# pHCircuit.net
KiCad netlist of a schematic drawn in Altium Designer
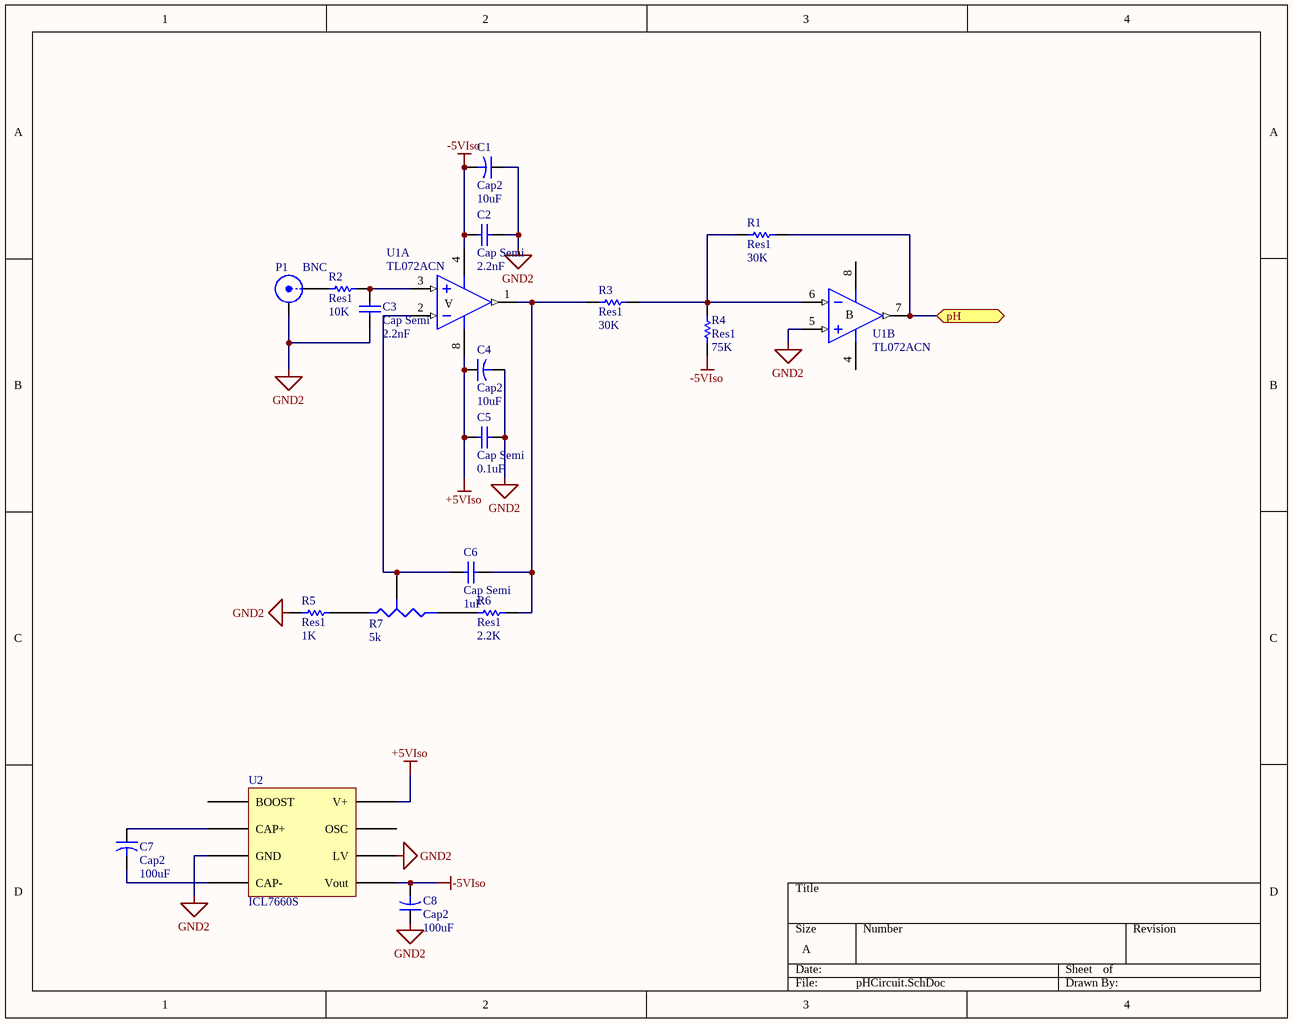
[diagram p0: pHCircuit.SchDoc]

(export (version "E")
  (design (tool "Eeschema 10.0.6"))
  (components
    (comp (ref "C1")
      (value "Cap2")
      (footprint "CAPC3216L")
      (description "Capacitor")
      (fields (field (name "ALTIUM_VALUE") "10uF") (field (name "PUBLISHER") "Altium Limited"))
      (libsource (lib "Miscellaneous Devices") (part "Cap2"))
    )
    (comp (ref "C2")
      (value "Cap Semi")
      (footprint "RESC2012L")
      (description "Capacitor (Semiconductor SIM Model)")
      (fields (field (name "ALTIUM_VALUE") "2.2nF") (field (name "PUBLISHER") "Altium Limited"))
      (libsource (lib "Miscellaneous Devices") (part "Cap Semi"))
    )
    (comp (ref "C3")
      (value "Cap Semi")
      (footprint "RESC2012L")
      (description "Capacitor (Semiconductor SIM Model)")
      (fields (field (name "ALTIUM_VALUE") "2.2nF") (field (name "PUBLISHER") "Altium Limited"))
      (libsource (lib "Miscellaneous Devices") (part "Cap Semi"))
    )
    (comp (ref "C4")
      (value "Cap2")
      (footprint "CAPC3216L")
      (description "Capacitor")
      (fields (field (name "ALTIUM_VALUE") "10uF") (field (name "PUBLISHER") "Altium Limited"))
      (libsource (lib "Miscellaneous Devices") (part "Cap2"))
    )
    (comp (ref "C5")
      (value "Cap Semi")
      (footprint "RESC2012L")
      (description "Capacitor (Semiconductor SIM Model)")
      (fields (field (name "ALTIUM_VALUE") "0.1uF") (field (name "PUBLISHER") "Altium Limited"))
      (libsource (lib "Miscellaneous Devices") (part "Cap Semi"))
    )
    (comp (ref "C6")
      (value "Cap Semi")
      (footprint "RESC2012L")
      (description "Capacitor (Semiconductor SIM Model)")
      (fields (field (name "ALTIUM_VALUE") "1uF") (field (name "PUBLISHER") "Altium Limited"))
      (libsource (lib "Miscellaneous Devices") (part "Cap Semi"))
    )
    (comp (ref "C7")
      (value "Cap2")
      (footprint "CAPC3216L")
      (description "Capacitor")
      (fields (field (name "ALTIUM_VALUE") "100uF") (field (name "PUBLISHER") "Altium Limited"))
      (libsource (lib "Miscellaneous Devices") (part "Cap2"))
    )
    (comp (ref "C8")
      (value "Cap2")
      (footprint "CAPC3216L")
      (description "Capacitor")
      (fields (field (name "ALTIUM_VALUE") "100uF") (field (name "PUBLISHER") "Altium Limited"))
      (libsource (lib "Miscellaneous Devices") (part "Cap2"))
    )
    (comp (ref "P1")
      (value "BNC")
      (footprint "BNC_RA CON")
      (description "BNC Elbow Connector")
      (fields (field (name "PUBLISHER") "Altium Limited"))
      (libsource (lib "Miscellaneous Connectors") (part "BNC"))
    )
    (comp (ref "R1")
      (value "Res1")
      (footprint "RESC2012L")
      (description "Resistor")
      (fields (field (name "ALTIUM_VALUE") "30K") (field (name "PUBLISHER") "Altium Limited"))
      (libsource (lib "Miscellaneous Devices") (part "Res1"))
    )
    (comp (ref "R2")
      (value "Res1")
      (footprint "RESC2012L")
      (description "Resistor")
      (fields (field (name "ALTIUM_VALUE") "10K") (field (name "PUBLISHER") "Altium Limited"))
      (libsource (lib "Miscellaneous Devices") (part "Res1"))
    )
    (comp (ref "R3")
      (value "Res1")
      (footprint "RESC2012L")
      (description "Resistor")
      (fields (field (name "ALTIUM_VALUE") "30K") (field (name "PUBLISHER") "Altium Limited"))
      (libsource (lib "Miscellaneous Devices") (part "Res1"))
    )
    (comp (ref "R4")
      (value "Res1")
      (footprint "RESC2012L")
      (description "Resistor")
      (fields (field (name "ALTIUM_VALUE") "75K") (field (name "PUBLISHER") "Altium Limited"))
      (libsource (lib "Miscellaneous Devices") (part "Res1"))
    )
    (comp (ref "R5")
      (value "Res1")
      (footprint "RESC2012L")
      (description "Resistor")
      (fields (field (name "ALTIUM_VALUE") "1K") (field (name "PUBLISHER") "Altium Limited"))
      (libsource (lib "Miscellaneous Devices") (part "Res1"))
    )
    (comp (ref "R6")
      (value "Res1")
      (footprint "RESC2012L")
      (description "Resistor")
      (fields (field (name "ALTIUM_VALUE") "2.2K") (field (name "PUBLISHER") "Altium Limited"))
      (libsource (lib "Miscellaneous Devices") (part "Res1"))
    )
    (comp (ref "R7") (value "5k") (footprint "R25_turn_Top") (libsource (lib "PCHOTNew") (part "R25_turn")))
    (comp (ref "U1")
      (value "TL072ACN")
      (footprint "DIP8")
      (description "Low-Noise J-FET Dual Operational Amplifier")
      (fields (field (name "PUBLISHER") "Altium Limited"))
      (libsource (lib "ST Operational Amplifier") (part "TL072ACN"))
    )
    (comp (ref "U2")
      (value "ICL7660S")
      (footprint "ST Operational Amplifier:DIP8")
      (libsource (lib "PCHOTNew") (part "ICL7660S"))
    )
  )
  (nets
    (net (code "1") (name "+5VIso") (class "Default")
      (node (ref "C4") (pin "1") (pinfunction "1_1") (pintype "passive"))
      (node (ref "C5") (pin "2") (pinfunction "2_2") (pintype "passive"))
      (node (ref "U1") (pin "8") (pinfunction "V+_8") (pintype "power_in"))
      (node (ref "U2") (pin "8") (pinfunction "V+_8") (pintype "passive"))
    )
    (net (code "2") (name "-5VIso") (class "Default")
      (node (ref "C1") (pin "2") (pinfunction "2_2") (pintype "passive"))
      (node (ref "C2") (pin "2") (pinfunction "2_2") (pintype "passive"))
      (node (ref "C8") (pin "2") (pinfunction "2_2") (pintype "passive"))
      (node (ref "R4") (pin "1") (pinfunction "1_1") (pintype "passive"))
      (node (ref "U1") (pin "4") (pinfunction "V-_4") (pintype "power_in"))
      (node (ref "U2") (pin "5") (pinfunction "Vout_5") (pintype "passive"))
    )
    (net (code "3") (name "/pH") (class "Default")
      (node (ref "R1") (pin "1") (pinfunction "1_1") (pintype "passive"))
      (node (ref "U1") (pin "7") (pinfunction "OUT_7") (pintype "output"))
    )
    (net (code "4") (name "GND2") (class "Default")
      (node (ref "C1") (pin "1") (pinfunction "1_1") (pintype "passive"))
      (node (ref "C2") (pin "1") (pinfunction "1_1") (pintype "passive"))
      (node (ref "C3") (pin "1") (pinfunction "1_1") (pintype "passive"))
      (node (ref "C4") (pin "2") (pinfunction "2_2") (pintype "passive"))
      (node (ref "C5") (pin "1") (pinfunction "1_1") (pintype "passive"))
      (node (ref "C8") (pin "1") (pinfunction "1_1") (pintype "passive"))
      (node (ref "P1") (pin "2") (pinfunction "Y_2") (pintype "passive"))
      (node (ref "R5") (pin "2") (pinfunction "2_2") (pintype "passive"))
      (node (ref "U1") (pin "5") (pinfunction "IN+_5") (pintype "input"))
      (node (ref "U2") (pin "3") (pinfunction "GND_3") (pintype "passive"))
      (node (ref "U2") (pin "6") (pinfunction "LV_6") (pintype "passive"))
    )
    (net (code "5") (name "Net-(P1-X)") (class "Default")
      (node (ref "P1") (pin "1") (pinfunction "X_1") (pintype "passive"))
      (node (ref "R2") (pin "2") (pinfunction "2_2") (pintype "passive"))
    )
    (net (code "6") (name "Net-(R7-A)") (class "Default")
      (node (ref "R5") (pin "1") (pinfunction "1_1") (pintype "passive"))
      (node (ref "R7") (pin "1") (pinfunction "A_1") (pintype "passive"))
    )
    (net (code "7") (name "Net-(R7-B)") (class "Default")
      (node (ref "R6") (pin "2") (pinfunction "2_2") (pintype "passive"))
      (node (ref "R7") (pin "2") (pinfunction "B_2") (pintype "passive"))
    )
    (net (code "8") (name "Net-(R7-TAP)") (class "Default")
      (node (ref "C6") (pin "2") (pinfunction "2_2") (pintype "passive"))
      (node (ref "R7") (pin "3") (pinfunction "TAP_3") (pintype "passive"))
      (node (ref "U1") (pin "2") (pinfunction "IN-_2") (pintype "input"))
    )
    (net (code "9") (name "Net-(U1A-IN+)") (class "Default")
      (node (ref "C3") (pin "2") (pinfunction "2_2") (pintype "passive"))
      (node (ref "R2") (pin "1") (pinfunction "1_1") (pintype "passive"))
      (node (ref "U1") (pin "3") (pinfunction "IN+_3") (pintype "input"))
    )
    (net (code "10") (name "Net-(U1A-OUT)") (class "Default")
      (node (ref "C6") (pin "1") (pinfunction "1_1") (pintype "passive"))
      (node (ref "R3") (pin "2") (pinfunction "2_2") (pintype "passive"))
      (node (ref "R6") (pin "1") (pinfunction "1_1") (pintype "passive"))
      (node (ref "U1") (pin "1") (pinfunction "OUT_1") (pintype "output"))
    )
    (net (code "11") (name "Net-(U1B-IN-)") (class "Default")
      (node (ref "R1") (pin "2") (pinfunction "2_2") (pintype "passive"))
      (node (ref "R3") (pin "1") (pinfunction "1_1") (pintype "passive"))
      (node (ref "R4") (pin "2") (pinfunction "2_2") (pintype "passive"))
      (node (ref "U1") (pin "6") (pinfunction "IN-_6") (pintype "input"))
    )
    (net (code "12") (name "Net-(U2-CAP+)") (class "Default")
      (node (ref "C7") (pin "1") (pinfunction "1_1") (pintype "passive"))
      (node (ref "U2") (pin "2") (pinfunction "CAP+_2") (pintype "passive"))
    )
    (net (code "13") (name "Net-(U2-CAP-)") (class "Default")
      (node (ref "C7") (pin "2") (pinfunction "2_2") (pintype "passive"))
      (node (ref "U2") (pin "4") (pinfunction "CAP-_4") (pintype "passive"))
    )
    (net (code "14") (name "unconnected-(U1B-V+-Pad8)") (class "Default")
      (node (ref "U1") (pin "8") (pinfunction "V+_8") (pintype "power_in"))
    )
    (net (code "15") (name "unconnected-(U1B-V--Pad4)") (class "Default")
      (node (ref "U1") (pin "4") (pinfunction "V-_4") (pintype "power_in"))
    )
    (net (code "16") (name "unconnected-(U2-BOOST-Pad1)") (class "Default")
      (node (ref "U2") (pin "1") (pinfunction "BOOST_1") (pintype "passive"))
    )
    (net (code "17") (name "unconnected-(U2-OSC-Pad7)") (class "Default")
      (node (ref "U2") (pin "7") (pinfunction "OSC_7") (pintype "passive"))
    )
  )
)
